# SCH_Electronica-Digital-Corte-3-Sara-Nu_.net
KiCad netlist of a schematic drawn in EasyEDA
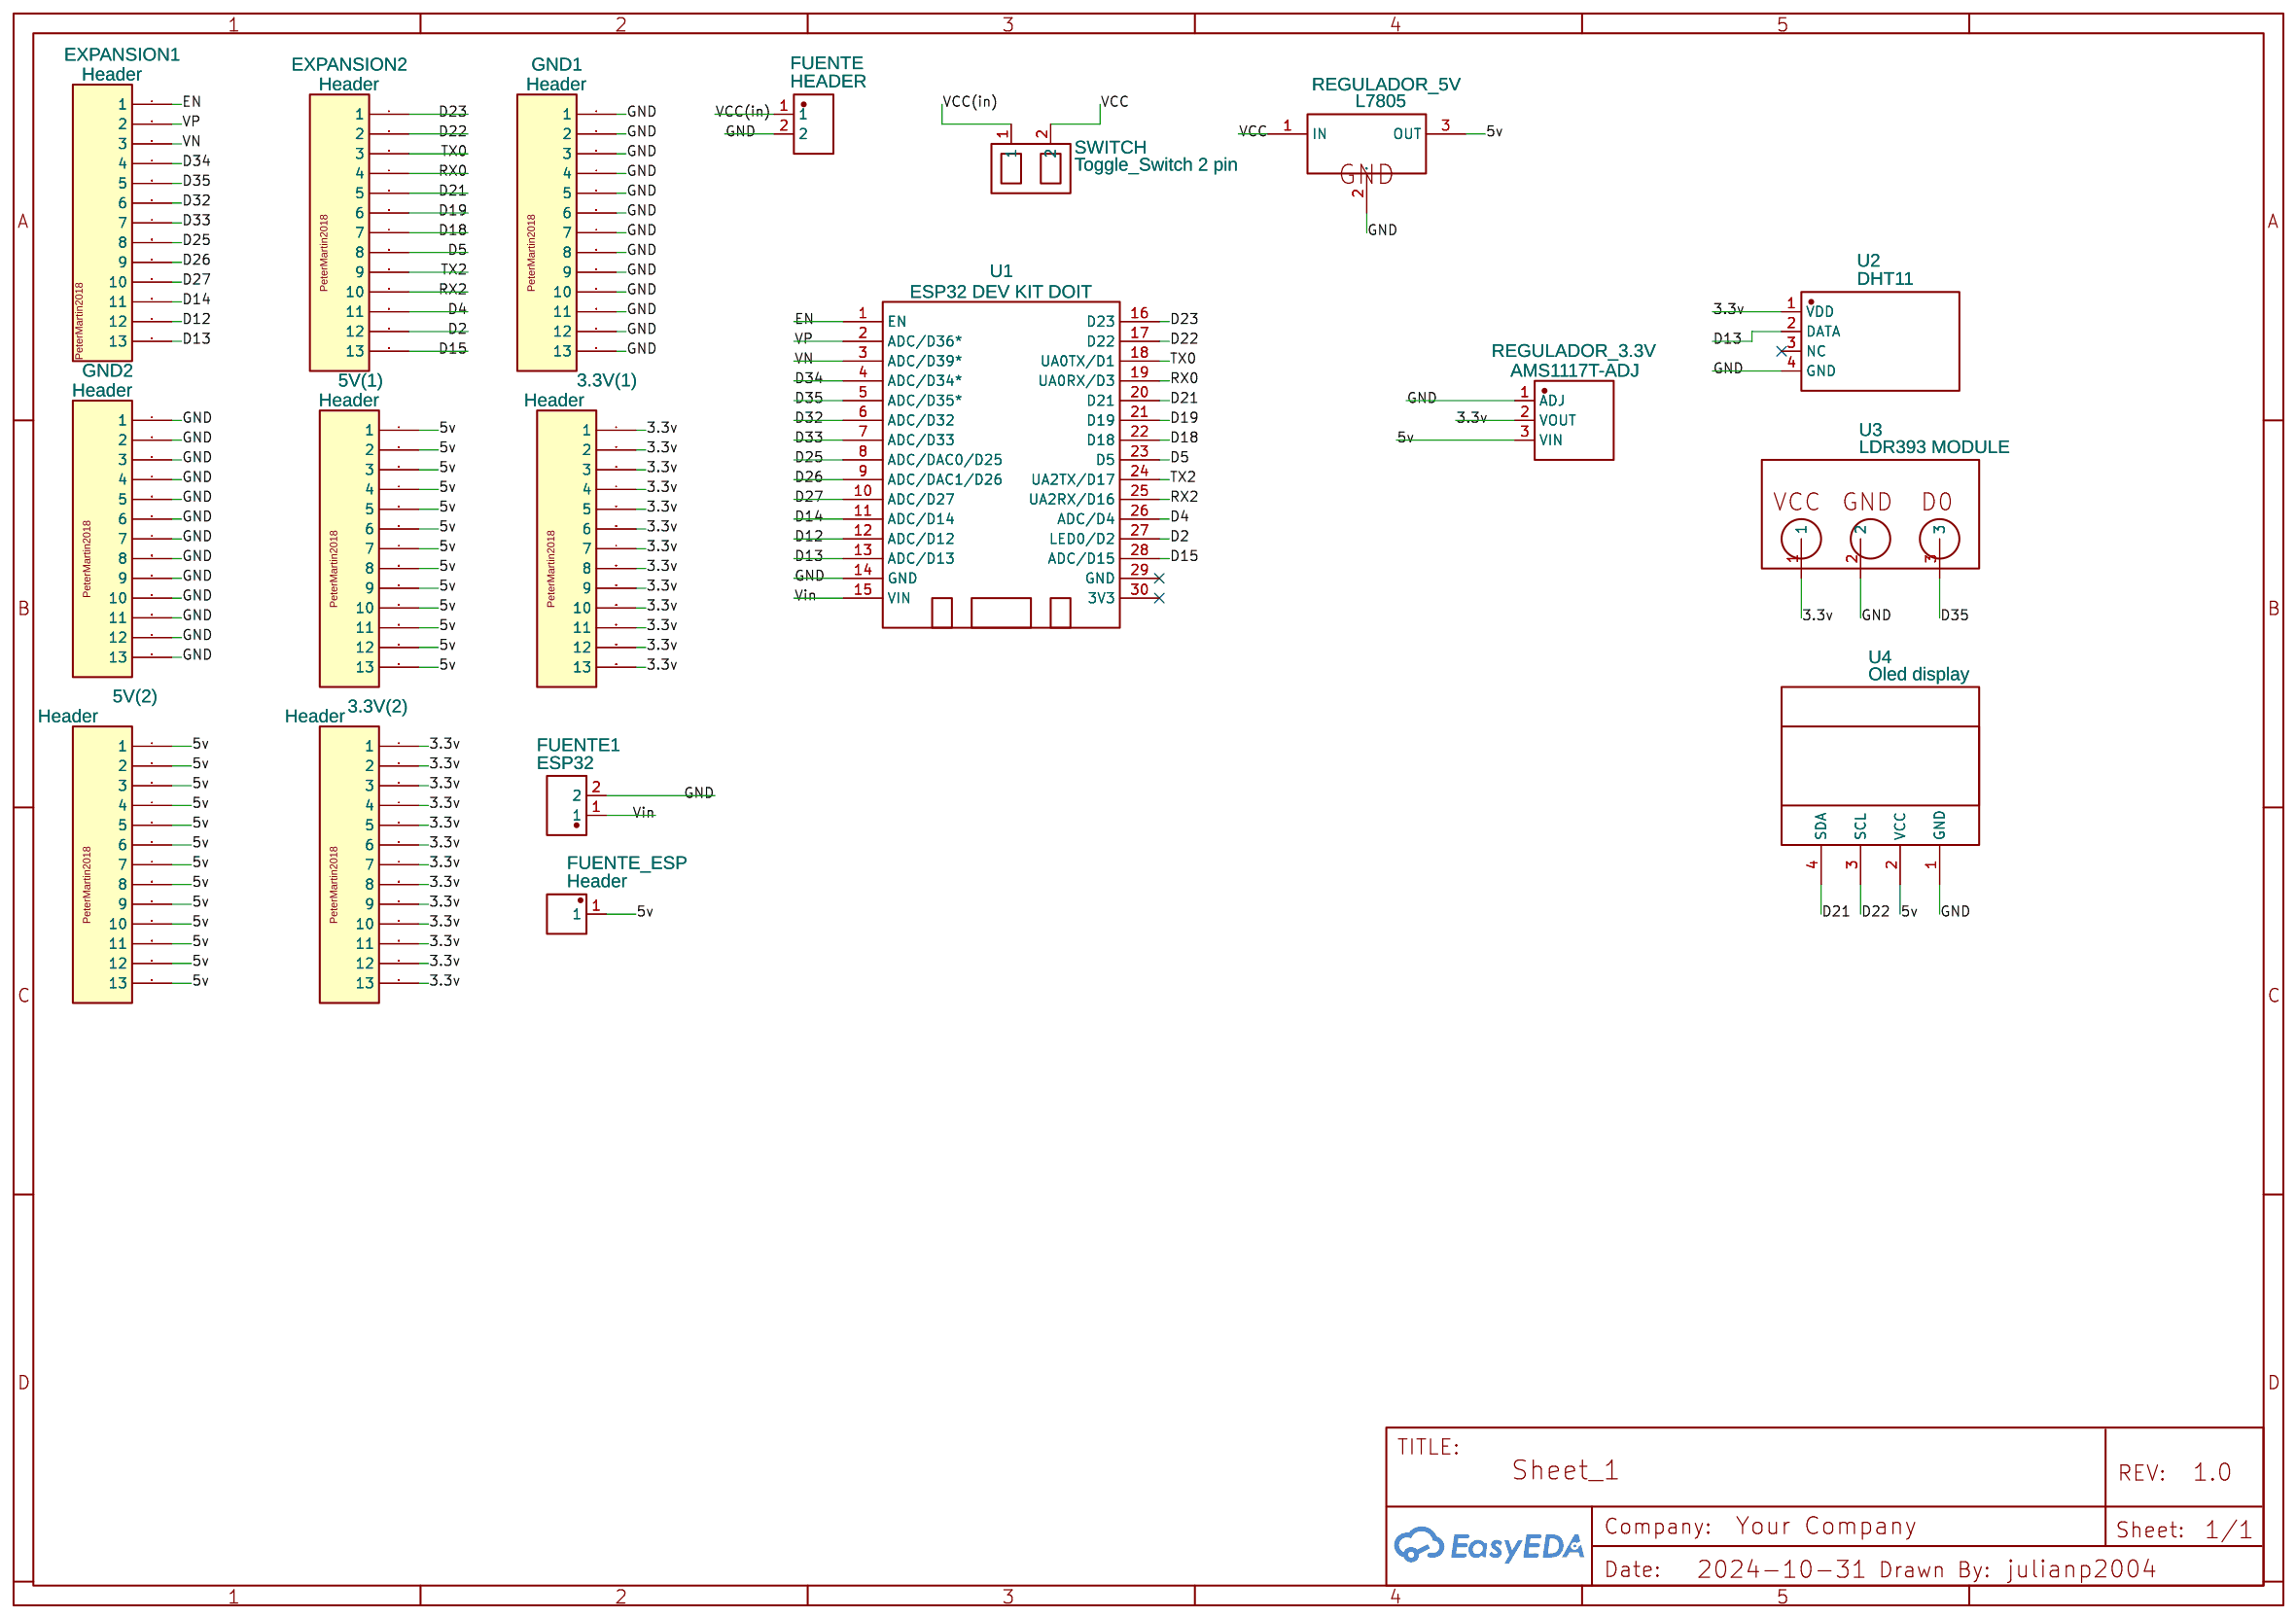
[diagram p0: schematic sheet]

(export (version "E")
  (design (tool "Eeschema 10.0.6"))
  (components
    (comp (ref "3.3V(1)")
      (value "Header")
      (fields (field (name "Manufacturer Part") "Altronics"))
      (libsource (lib "") (part "Header 13 copy_3"))
    )
    (comp (ref "3.3V(2)")
      (value "Header")
      (fields (field (name "Manufacturer Part") "Altronics"))
      (libsource (lib "") (part "Header 13 copy_5"))
    )
    (comp (ref "5V(1)")
      (value "Header")
      (fields (field (name "Manufacturer Part") "Altronics"))
      (libsource (lib "") (part "Header 13 copy_1"))
    )
    (comp (ref "5V(2)")
      (value "Header")
      (fields (field (name "Manufacturer Part") "Altronics"))
      (libsource (lib "") (part "Header 13 copy_6"))
    )
    (comp (ref "EXPANSION1")
      (value "Header")
      (fields (field (name "Manufacturer Part") "Altronics"))
      (libsource (lib "") (part "Header 13 copy_4"))
    )
    (comp (ref "EXPANSION2")
      (value "Header")
      (fields (field (name "Manufacturer Part") "Altronics"))
      (libsource (lib "") (part "Header 13 copy_2"))
    )
    (comp (ref "FUENTE") (value "HEADER") (libsource (lib "") (part "PIN HEADER MACHO 1X2 180_1")))
    (comp (ref "FUENTE1") (value "ESP32") (libsource (lib "") (part "PIN HEADER MACHO 1X2 180")))
    (comp (ref "FUENTE_ESP") (value "Header") (libsource (lib "") (part "HEADER - 2.54_1X1 FEM COPY")))
    (comp (ref "GND1")
      (value "Header")
      (fields (field (name "Manufacturer Part") "Altronics"))
      (libsource (lib "") (part "Header 13 copy"))
    )
    (comp (ref "GND2")
      (value "Header")
      (fields (field (name "Manufacturer Part") "Altronics"))
      (libsource (lib "") (part "Header 13 copy"))
    )
    (comp (ref "REGULADOR_3.3V")
      (value "AMS1117T-ADJ")
      (fields (field (name "Manufacturer") "HGC(华冠)"))
      (libsource (lib "") (part "AMS1117T-ADJ"))
    )
    (comp (ref "REGULADOR_5V")
      (value "L7805")
      (fields
        (field (name "Manufacturer Part") "L7805CV-HXY")
        (field (name "Manufacturer") "HXY MOSFET(华轩阳电子)")
      )
      (libsource (lib "") (part "L7805CV-HXY"))
    )
    (comp (ref "SWITCH") (value "Toggle_Switch 2 pin") (libsource (lib "") (part "Toggle_Switch 2 pin")))
    (comp (ref "U1") (value "ESP32 DEV KIT DOIT") (libsource (lib "") (part "ESP32 DEV KIT DOIT")))
    (comp (ref "U2")
      (value "DHT11")
      (fields (field (name "Manufacturer") "广州奥松"))
      (libsource (lib "") (part "DHT11"))
    )
    (comp (ref "U3") (value "LDR393 MODULE") (libsource (lib "") (part "LDR393 MODULE")))
    (comp (ref "U4") (value "Oled display") (libsource (lib "") (part "Oled display")))
  )
  (nets
    (net (code "1") (name "/3.3v") (class "Default")
      (node (ref "3.3V(1)") (pin "1") (pinfunction "1_1") (pintype "unspecified"))
      (node (ref "3.3V(1)") (pin "10") (pinfunction "10_10") (pintype "unspecified"))
      (node (ref "3.3V(1)") (pin "11") (pinfunction "11_11") (pintype "unspecified"))
      (node (ref "3.3V(1)") (pin "12") (pinfunction "12_12") (pintype "unspecified"))
      (node (ref "3.3V(1)") (pin "13") (pinfunction "13_13") (pintype "unspecified"))
      (node (ref "3.3V(1)") (pin "2") (pinfunction "2_2") (pintype "unspecified"))
      (node (ref "3.3V(1)") (pin "3") (pinfunction "3_3") (pintype "unspecified"))
      (node (ref "3.3V(1)") (pin "4") (pinfunction "4_4") (pintype "unspecified"))
      (node (ref "3.3V(1)") (pin "5") (pinfunction "5_5") (pintype "unspecified"))
      (node (ref "3.3V(1)") (pin "6") (pinfunction "6_6") (pintype "unspecified"))
      (node (ref "3.3V(1)") (pin "7") (pinfunction "7_7") (pintype "unspecified"))
      (node (ref "3.3V(1)") (pin "8") (pinfunction "8_8") (pintype "unspecified"))
      (node (ref "3.3V(1)") (pin "9") (pinfunction "9_9") (pintype "unspecified"))
      (node (ref "3.3V(2)") (pin "1") (pinfunction "1_1") (pintype "unspecified"))
      (node (ref "3.3V(2)") (pin "10") (pinfunction "10_10") (pintype "unspecified"))
      (node (ref "3.3V(2)") (pin "11") (pinfunction "11_11") (pintype "unspecified"))
      (node (ref "3.3V(2)") (pin "12") (pinfunction "12_12") (pintype "unspecified"))
      (node (ref "3.3V(2)") (pin "13") (pinfunction "13_13") (pintype "unspecified"))
      (node (ref "3.3V(2)") (pin "2") (pinfunction "2_2") (pintype "unspecified"))
      (node (ref "3.3V(2)") (pin "3") (pinfunction "3_3") (pintype "unspecified"))
      (node (ref "3.3V(2)") (pin "4") (pinfunction "4_4") (pintype "unspecified"))
      (node (ref "3.3V(2)") (pin "5") (pinfunction "5_5") (pintype "unspecified"))
      (node (ref "3.3V(2)") (pin "6") (pinfunction "6_6") (pintype "unspecified"))
      (node (ref "3.3V(2)") (pin "7") (pinfunction "7_7") (pintype "unspecified"))
      (node (ref "3.3V(2)") (pin "8") (pinfunction "8_8") (pintype "unspecified"))
      (node (ref "3.3V(2)") (pin "9") (pinfunction "9_9") (pintype "unspecified"))
      (node (ref "REGULADOR_3.3V") (pin "2") (pinfunction "VOUT_2") (pintype "unspecified"))
      (node (ref "U2") (pin "1") (pinfunction "VDD_1") (pintype "unspecified"))
      (node (ref "U3") (pin "1") (pinfunction "1_1") (pintype "unspecified"))
    )
    (net (code "2") (name "/5v") (class "Default")
      (node (ref "5V(1)") (pin "1") (pinfunction "1_1") (pintype "unspecified"))
      (node (ref "5V(1)") (pin "10") (pinfunction "10_10") (pintype "unspecified"))
      (node (ref "5V(1)") (pin "11") (pinfunction "11_11") (pintype "unspecified"))
      (node (ref "5V(1)") (pin "12") (pinfunction "12_12") (pintype "unspecified"))
      (node (ref "5V(1)") (pin "13") (pinfunction "13_13") (pintype "unspecified"))
      (node (ref "5V(1)") (pin "2") (pinfunction "2_2") (pintype "unspecified"))
      (node (ref "5V(1)") (pin "3") (pinfunction "3_3") (pintype "unspecified"))
      (node (ref "5V(1)") (pin "4") (pinfunction "4_4") (pintype "unspecified"))
      (node (ref "5V(1)") (pin "5") (pinfunction "5_5") (pintype "unspecified"))
      (node (ref "5V(1)") (pin "6") (pinfunction "6_6") (pintype "unspecified"))
      (node (ref "5V(1)") (pin "7") (pinfunction "7_7") (pintype "unspecified"))
      (node (ref "5V(1)") (pin "8") (pinfunction "8_8") (pintype "unspecified"))
      (node (ref "5V(1)") (pin "9") (pinfunction "9_9") (pintype "unspecified"))
      (node (ref "5V(2)") (pin "1") (pinfunction "1_1") (pintype "unspecified"))
      (node (ref "5V(2)") (pin "10") (pinfunction "10_10") (pintype "unspecified"))
      (node (ref "5V(2)") (pin "11") (pinfunction "11_11") (pintype "unspecified"))
      (node (ref "5V(2)") (pin "12") (pinfunction "12_12") (pintype "unspecified"))
      (node (ref "5V(2)") (pin "13") (pinfunction "13_13") (pintype "unspecified"))
      (node (ref "5V(2)") (pin "2") (pinfunction "2_2") (pintype "unspecified"))
      (node (ref "5V(2)") (pin "3") (pinfunction "3_3") (pintype "unspecified"))
      (node (ref "5V(2)") (pin "4") (pinfunction "4_4") (pintype "unspecified"))
      (node (ref "5V(2)") (pin "5") (pinfunction "5_5") (pintype "unspecified"))
      (node (ref "5V(2)") (pin "6") (pinfunction "6_6") (pintype "unspecified"))
      (node (ref "5V(2)") (pin "7") (pinfunction "7_7") (pintype "unspecified"))
      (node (ref "5V(2)") (pin "8") (pinfunction "8_8") (pintype "unspecified"))
      (node (ref "5V(2)") (pin "9") (pinfunction "9_9") (pintype "unspecified"))
      (node (ref "FUENTE_ESP") (pin "1") (pinfunction "1_1") (pintype "unspecified"))
      (node (ref "REGULADOR_3.3V") (pin "3") (pinfunction "VIN_3") (pintype "unspecified"))
      (node (ref "REGULADOR_5V") (pin "3") (pinfunction "OUT_3") (pintype "passive"))
      (node (ref "U4") (pin "2") (pinfunction "VCC_2") (pintype "unspecified"))
    )
    (net (code "3") (name "/D2") (class "Default")
      (node (ref "EXPANSION2") (pin "12") (pinfunction "12_12") (pintype "unspecified"))
      (node (ref "U1") (pin "27") (pinfunction "LED0/D2_27") (pintype "bidirectional"))
    )
    (net (code "4") (name "/D4") (class "Default")
      (node (ref "EXPANSION2") (pin "11") (pinfunction "11_11") (pintype "unspecified"))
      (node (ref "U1") (pin "26") (pinfunction "ADC/D4_26") (pintype "bidirectional"))
    )
    (net (code "5") (name "/D5") (class "Default")
      (node (ref "EXPANSION2") (pin "8") (pinfunction "8_8") (pintype "unspecified"))
      (node (ref "U1") (pin "23") (pinfunction "D5_23") (pintype "bidirectional"))
    )
    (net (code "6") (name "/D12") (class "Default")
      (node (ref "EXPANSION1") (pin "12") (pinfunction "12_12") (pintype "unspecified"))
      (node (ref "U1") (pin "12") (pinfunction "ADC/D12_12") (pintype "bidirectional"))
    )
    (net (code "7") (name "/D13") (class "Default")
      (node (ref "EXPANSION1") (pin "13") (pinfunction "13_13") (pintype "unspecified"))
      (node (ref "U1") (pin "13") (pinfunction "ADC/D13_13") (pintype "bidirectional"))
      (node (ref "U2") (pin "2") (pinfunction "DATA_2") (pintype "unspecified"))
    )
    (net (code "8") (name "/D14") (class "Default")
      (node (ref "EXPANSION1") (pin "11") (pinfunction "11_11") (pintype "unspecified"))
      (node (ref "U1") (pin "11") (pinfunction "ADC/D14_11") (pintype "bidirectional"))
    )
    (net (code "9") (name "/D15") (class "Default")
      (node (ref "EXPANSION2") (pin "13") (pinfunction "13_13") (pintype "unspecified"))
      (node (ref "U1") (pin "28") (pinfunction "ADC/D15_28") (pintype "bidirectional"))
    )
    (net (code "10") (name "/D18") (class "Default")
      (node (ref "EXPANSION2") (pin "7") (pinfunction "7_7") (pintype "unspecified"))
      (node (ref "U1") (pin "22") (pinfunction "D18_22") (pintype "bidirectional"))
    )
    (net (code "11") (name "/D19") (class "Default")
      (node (ref "EXPANSION2") (pin "6") (pinfunction "6_6") (pintype "unspecified"))
      (node (ref "U1") (pin "21") (pinfunction "D19_21") (pintype "bidirectional"))
    )
    (net (code "12") (name "/D21") (class "Default")
      (node (ref "EXPANSION2") (pin "5") (pinfunction "5_5") (pintype "unspecified"))
      (node (ref "U1") (pin "20") (pinfunction "D21_20") (pintype "bidirectional"))
      (node (ref "U4") (pin "4") (pinfunction "SDA_4") (pintype "unspecified"))
    )
    (net (code "13") (name "/D22") (class "Default")
      (node (ref "EXPANSION2") (pin "2") (pinfunction "2_2") (pintype "unspecified"))
      (node (ref "U1") (pin "17") (pinfunction "D22_17") (pintype "bidirectional"))
      (node (ref "U4") (pin "3") (pinfunction "SCL_3") (pintype "unspecified"))
    )
    (net (code "14") (name "/D23") (class "Default")
      (node (ref "EXPANSION2") (pin "1") (pinfunction "1_1") (pintype "unspecified"))
      (node (ref "U1") (pin "16") (pinfunction "D23_16") (pintype "bidirectional"))
    )
    (net (code "15") (name "/D25") (class "Default")
      (node (ref "EXPANSION1") (pin "8") (pinfunction "8_8") (pintype "unspecified"))
      (node (ref "U1") (pin "8") (pinfunction "ADC/DAC0/D25_8") (pintype "bidirectional"))
    )
    (net (code "16") (name "/D26") (class "Default")
      (node (ref "EXPANSION1") (pin "9") (pinfunction "9_9") (pintype "unspecified"))
      (node (ref "U1") (pin "9") (pinfunction "ADC/DAC1/D26_9") (pintype "bidirectional"))
    )
    (net (code "17") (name "/D27") (class "Default")
      (node (ref "EXPANSION1") (pin "10") (pinfunction "10_10") (pintype "unspecified"))
      (node (ref "U1") (pin "10") (pinfunction "ADC/D27_10") (pintype "bidirectional"))
    )
    (net (code "18") (name "/D32") (class "Default")
      (node (ref "EXPANSION1") (pin "6") (pinfunction "6_6") (pintype "unspecified"))
      (node (ref "U1") (pin "6") (pinfunction "ADC/D32_6") (pintype "bidirectional"))
    )
    (net (code "19") (name "/D33") (class "Default")
      (node (ref "EXPANSION1") (pin "7") (pinfunction "7_7") (pintype "unspecified"))
      (node (ref "U1") (pin "7") (pinfunction "ADC/D33_7") (pintype "bidirectional"))
    )
    (net (code "20") (name "/D34") (class "Default")
      (node (ref "EXPANSION1") (pin "4") (pinfunction "4_4") (pintype "unspecified"))
      (node (ref "U1") (pin "4") (pinfunction "ADC/D34*_4") (pintype "input"))
    )
    (net (code "21") (name "/D35") (class "Default")
      (node (ref "EXPANSION1") (pin "5") (pinfunction "5_5") (pintype "unspecified"))
      (node (ref "U1") (pin "5") (pinfunction "ADC/D35*_5") (pintype "input"))
      (node (ref "U3") (pin "3") (pinfunction "3_3") (pintype "unspecified"))
    )
    (net (code "22") (name "/EN") (class "Default")
      (node (ref "EXPANSION1") (pin "1") (pinfunction "1_1") (pintype "unspecified"))
      (node (ref "U1") (pin "1") (pinfunction "EN_1") (pintype "bidirectional"))
    )
    (net (code "23") (name "/GND") (class "Default")
      (node (ref "FUENTE") (pin "2") (pinfunction "2_2") (pintype "unspecified"))
      (node (ref "FUENTE1") (pin "2") (pinfunction "2_2") (pintype "unspecified"))
      (node (ref "GND1") (pin "1") (pinfunction "1_1") (pintype "unspecified"))
      (node (ref "GND1") (pin "10") (pinfunction "10_10") (pintype "unspecified"))
      (node (ref "GND1") (pin "11") (pinfunction "11_11") (pintype "unspecified"))
      (node (ref "GND1") (pin "12") (pinfunction "12_12") (pintype "unspecified"))
      (node (ref "GND1") (pin "13") (pinfunction "13_13") (pintype "unspecified"))
      (node (ref "GND1") (pin "2") (pinfunction "2_2") (pintype "unspecified"))
      (node (ref "GND1") (pin "3") (pinfunction "3_3") (pintype "unspecified"))
      (node (ref "GND1") (pin "4") (pinfunction "4_4") (pintype "unspecified"))
      (node (ref "GND1") (pin "5") (pinfunction "5_5") (pintype "unspecified"))
      (node (ref "GND1") (pin "6") (pinfunction "6_6") (pintype "unspecified"))
      (node (ref "GND1") (pin "7") (pinfunction "7_7") (pintype "unspecified"))
      (node (ref "GND1") (pin "8") (pinfunction "8_8") (pintype "unspecified"))
      (node (ref "GND1") (pin "9") (pinfunction "9_9") (pintype "unspecified"))
      (node (ref "GND2") (pin "1") (pinfunction "1_1") (pintype "unspecified"))
      (node (ref "GND2") (pin "10") (pinfunction "10_10") (pintype "unspecified"))
      (node (ref "GND2") (pin "11") (pinfunction "11_11") (pintype "unspecified"))
      (node (ref "GND2") (pin "12") (pinfunction "12_12") (pintype "unspecified"))
      (node (ref "GND2") (pin "13") (pinfunction "13_13") (pintype "unspecified"))
      (node (ref "GND2") (pin "2") (pinfunction "2_2") (pintype "unspecified"))
      (node (ref "GND2") (pin "3") (pinfunction "3_3") (pintype "unspecified"))
      (node (ref "GND2") (pin "4") (pinfunction "4_4") (pintype "unspecified"))
      (node (ref "GND2") (pin "5") (pinfunction "5_5") (pintype "unspecified"))
      (node (ref "GND2") (pin "6") (pinfunction "6_6") (pintype "unspecified"))
      (node (ref "GND2") (pin "7") (pinfunction "7_7") (pintype "unspecified"))
      (node (ref "GND2") (pin "8") (pinfunction "8_8") (pintype "unspecified"))
      (node (ref "GND2") (pin "9") (pinfunction "9_9") (pintype "unspecified"))
      (node (ref "REGULADOR_3.3V") (pin "1") (pinfunction "ADJ_1") (pintype "unspecified"))
      (node (ref "REGULADOR_5V") (pin "2") (pinfunction "GND_2") (pintype "passive"))
      (node (ref "U1") (pin "14") (pinfunction "GND_14") (pintype "bidirectional"))
      (node (ref "U2") (pin "4") (pinfunction "GND_4") (pintype "unspecified"))
      (node (ref "U3") (pin "2") (pinfunction "2_2") (pintype "unspecified"))
      (node (ref "U4") (pin "1") (pinfunction "GND_1") (pintype "unspecified"))
    )
    (net (code "24") (name "/RX0") (class "Default")
      (node (ref "EXPANSION2") (pin "4") (pinfunction "4_4") (pintype "unspecified"))
      (node (ref "U1") (pin "19") (pinfunction "UA0RX/D3_19") (pintype "bidirectional"))
    )
    (net (code "25") (name "/RX2") (class "Default")
      (node (ref "EXPANSION2") (pin "10") (pinfunction "10_10") (pintype "unspecified"))
      (node (ref "U1") (pin "25") (pinfunction "UA2RX/D16_25") (pintype "bidirectional"))
    )
    (net (code "26") (name "/TX0") (class "Default")
      (node (ref "EXPANSION2") (pin "3") (pinfunction "3_3") (pintype "unspecified"))
      (node (ref "U1") (pin "18") (pinfunction "UA0TX/D1_18") (pintype "bidirectional"))
    )
    (net (code "27") (name "/TX2") (class "Default")
      (node (ref "EXPANSION2") (pin "9") (pinfunction "9_9") (pintype "unspecified"))
      (node (ref "U1") (pin "24") (pinfunction "UA2TX/D17_24") (pintype "bidirectional"))
    )
    (net (code "28") (name "/VCC") (class "Default")
      (node (ref "REGULADOR_5V") (pin "1") (pinfunction "IN_1") (pintype "passive"))
      (node (ref "SWITCH") (pin "2") (pinfunction "2_2") (pintype "unspecified"))
    )
    (net (code "29") (name "/VCC(in)") (class "Default")
      (node (ref "FUENTE") (pin "1") (pinfunction "1_1") (pintype "unspecified"))
      (node (ref "SWITCH") (pin "1") (pinfunction "1_1") (pintype "unspecified"))
    )
    (net (code "30") (name "/VN") (class "Default")
      (node (ref "EXPANSION1") (pin "3") (pinfunction "3_3") (pintype "unspecified"))
      (node (ref "U1") (pin "3") (pinfunction "ADC/D39*_3") (pintype "input"))
    )
    (net (code "31") (name "/VP") (class "Default")
      (node (ref "EXPANSION1") (pin "2") (pinfunction "2_2") (pintype "unspecified"))
      (node (ref "U1") (pin "2") (pinfunction "ADC/D36*_2") (pintype "input"))
    )
    (net (code "32") (name "/Vin") (class "Default")
      (node (ref "FUENTE1") (pin "1") (pinfunction "1_1") (pintype "unspecified"))
      (node (ref "U1") (pin "15") (pinfunction "VIN_15") (pintype "input"))
    )
    (net (code "33") (name "unconnected-(U1-3V3-Pad30)") (class "Default")
      (node (ref "U1") (pin "30") (pinfunction "3V3_30") (pintype "bidirectional+no_connect"))
    )
    (net (code "34") (name "unconnected-(U1-GND-Pad29)") (class "Default")
      (node (ref "U1") (pin "29") (pinfunction "GND_29") (pintype "bidirectional+no_connect"))
    )
    (net (code "35") (name "unconnected-(U2-NC-Pad3)") (class "Default")
      (node (ref "U2") (pin "3") (pinfunction "NC_3") (pintype "unspecified+no_connect"))
    )
  )
)
